# 2014_AlimBeaconEye.net
KiCad netlist of a schematic drawn in Altium Designer
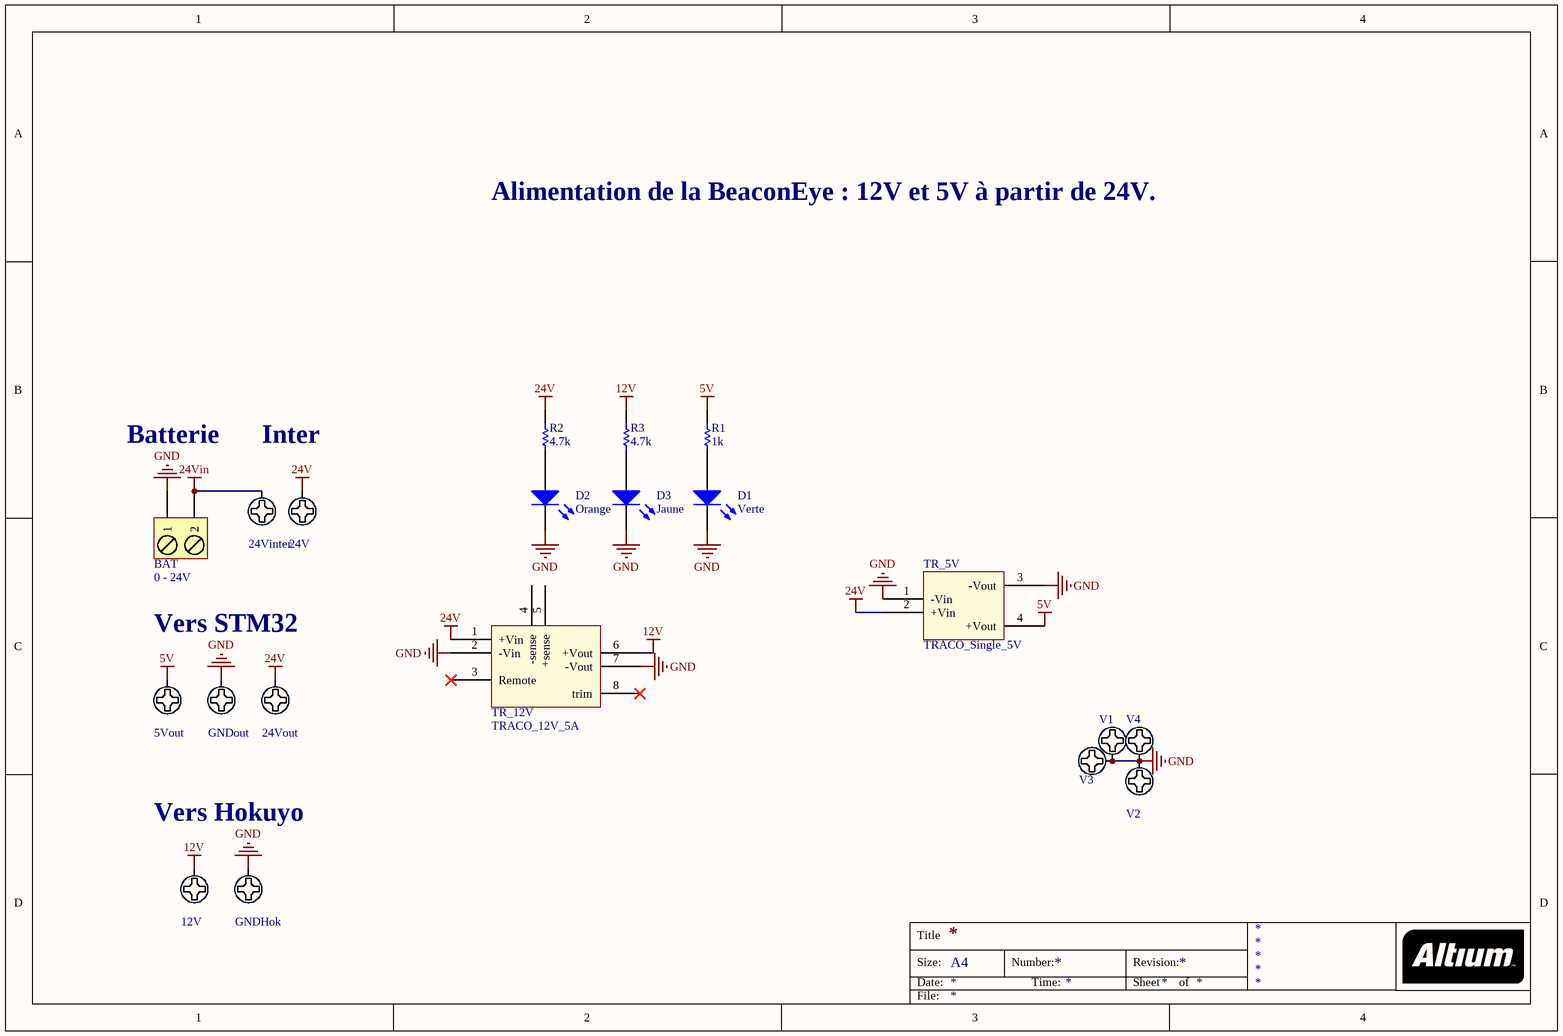
[diagram p0: 2014_AlimBeaconEye.SchDoc]

(export (version "E")
  (design (tool "Eeschema 10.0.6"))
  (components
    (comp (ref "5Vout")
      (value "Pad_M3")
      (footprint "M3x6mm")
      (description "Vis M3 X 6mm _TORX_Tête 6mm")
      (fields (field (name "PUBLISHER") "Damien Guitton"))
      (libsource (lib "_ROBOT") (part "Vis M3 X 6mm _TORX_Tête 6mm"))
    )
    (comp (ref "12V")
      (value "Pad_M3")
      (footprint "M3x6mm")
      (description "Vis M3 X 6mm _TORX_Tête 6mm")
      (fields (field (name "PUBLISHER") "Damien Guitton"))
      (libsource (lib "_ROBOT") (part "Vis M3 X 6mm _TORX_Tête 6mm"))
    )
    (comp (ref "24V")
      (value "Pad_M3")
      (footprint "M3x6mm")
      (description "Vis M3 X 6mm _TORX_Tête 6mm")
      (fields (field (name "PUBLISHER") "Damien Guitton"))
      (libsource (lib "_ROBOT") (part "Vis M3 X 6mm _TORX_Tête 6mm"))
    )
    (comp (ref "24Vinter")
      (value "Pad_M3")
      (footprint "M3x6mm")
      (description "Vis M3 X 6mm _TORX_Tête 6mm")
      (fields (field (name "PUBLISHER") "Damien Guitton"))
      (libsource (lib "_ROBOT") (part "Vis M3 X 6mm _TORX_Tête 6mm"))
    )
    (comp (ref "24Vout")
      (value "Pad_M3")
      (footprint "M3x6mm")
      (description "Vis M3 X 6mm _TORX_Tête 6mm")
      (fields (field (name "PUBLISHER") "Damien Guitton"))
      (libsource (lib "_ROBOT") (part "Vis M3 X 6mm _TORX_Tête 6mm"))
    )
    (comp (ref "BAT")
      (value "0 - 24V")
      (footprint "BORNIER2_FEM_COUDE")
      (description "Terminal blocks, 2 pins, pitch=5mm")
      (libsource (lib "miniprojet") (part "BORNIER2"))
    )
    (comp (ref "D1")
      (value "Verte")
      (footprint "LED_0805")
      (description "Typical LED")
      (fields (field (name "PUBLISHER") "Altium Limited"))
      (libsource (lib "_ROBOT") (part "LED"))
    )
    (comp (ref "D2")
      (value "Orange")
      (footprint "LED_0805")
      (description "Typical LED")
      (fields (field (name "PUBLISHER") "Altium Limited"))
      (libsource (lib "_ROBOT") (part "LED"))
    )
    (comp (ref "D3")
      (value "Jaune")
      (footprint "LED_0805")
      (description "Typical LED")
      (fields (field (name "PUBLISHER") "Altium Limited"))
      (libsource (lib "_ROBOT") (part "LED"))
    )
    (comp (ref "GNDHok")
      (value "Pad_M3")
      (footprint "M3x6mm")
      (description "Vis M3 X 6mm _TORX_Tête 6mm")
      (fields (field (name "PUBLISHER") "Damien Guitton"))
      (libsource (lib "_ROBOT") (part "Vis M3 X 6mm _TORX_Tête 6mm"))
    )
    (comp (ref "GNDout")
      (value "Pad_M3")
      (footprint "M3x6mm")
      (description "Vis M3 X 6mm _TORX_Tête 6mm")
      (fields (field (name "PUBLISHER") "Damien Guitton"))
      (libsource (lib "_ROBOT") (part "Vis M3 X 6mm _TORX_Tête 6mm"))
    )
    (comp (ref "R1")
      (value "1k")
      (footprint "R1206_N")
      (description "Resistor")
      (fields (field (name "PUBLISHER") "Altium Limited"))
      (libsource (lib "_ROBOT") (part "Resistor"))
    )
    (comp (ref "R2")
      (value "4.7k")
      (footprint "R1206_N")
      (description "Resistor")
      (fields (field (name "PUBLISHER") "Altium Limited"))
      (libsource (lib "_ROBOT") (part "Resistor"))
    )
    (comp (ref "R3")
      (value "4.7k")
      (footprint "R1206_N")
      (description "Resistor")
      (fields (field (name "PUBLISHER") "Altium Limited"))
      (libsource (lib "_ROBOT") (part "Resistor"))
    )
    (comp (ref "TR_5V")
      (value "TRACO_Single_5V")
      (footprint "TRACO_Single")
      (libsource (lib "Robot2010") (part "TRACO_Single"))
    )
    (comp (ref "TR_12V")
      (value "TRACO_12V_5A")
      (footprint "TRACO_SIMPLE_12V_5A")
      (libsource (lib "_ROBOT") (part "TRACO_12V_5A"))
    )
    (comp (ref "V1")
      (value "Pad_M3")
      (footprint "M3x6mm")
      (description "Vis M3 X 6mm _TORX_Tête 6mm")
      (fields (field (name "PUBLISHER") "Damien Guitton"))
      (libsource (lib "_ROBOT") (part "Vis M3 X 6mm _TORX_Tête 6mm"))
    )
    (comp (ref "V2")
      (value "Pad_M3")
      (footprint "M3x6mm")
      (description "Vis M3 X 6mm _TORX_Tête 6mm")
      (fields (field (name "PUBLISHER") "Damien Guitton"))
      (libsource (lib "_ROBOT") (part "Vis M3 X 6mm _TORX_Tête 6mm"))
    )
    (comp (ref "V3")
      (value "Pad_M3")
      (footprint "M3x6mm")
      (description "Vis M3 X 6mm _TORX_Tête 6mm")
      (fields (field (name "PUBLISHER") "Damien Guitton"))
      (libsource (lib "_ROBOT") (part "Vis M3 X 6mm _TORX_Tête 6mm"))
    )
    (comp (ref "V4")
      (value "Pad_M3")
      (footprint "M3x6mm")
      (description "Vis M3 X 6mm _TORX_Tête 6mm")
      (fields (field (name "PUBLISHER") "Damien Guitton"))
      (libsource (lib "_ROBOT") (part "Vis M3 X 6mm _TORX_Tête 6mm"))
    )
  )
  (nets
    (net (code "1") (name "5V") (class "Default")
      (node (ref "5Vout") (pin "1") (pinfunction "1_1") (pintype "passive"))
      (node (ref "R1") (pin "1") (pinfunction "1_1") (pintype "passive"))
      (node (ref "TR_5V") (pin "4") (pinfunction "+Vout_4") (pintype "passive"))
    )
    (net (code "2") (name "12V") (class "Default")
      (node (ref "12V") (pin "1") (pinfunction "1_1") (pintype "passive"))
      (node (ref "R3") (pin "1") (pinfunction "1_1") (pintype "passive"))
      (node (ref "TR_12V") (pin "6") (pinfunction "+Vout_6") (pintype "passive"))
    )
    (net (code "3") (name "24V") (class "Default")
      (node (ref "24V") (pin "1") (pinfunction "1_1") (pintype "passive"))
      (node (ref "24Vout") (pin "1") (pinfunction "1_1") (pintype "passive"))
      (node (ref "R2") (pin "1") (pinfunction "1_1") (pintype "passive"))
      (node (ref "TR_12V") (pin "1") (pinfunction "+Vin_1") (pintype "passive"))
      (node (ref "TR_5V") (pin "2") (pinfunction "+Vin_2") (pintype "passive"))
    )
    (net (code "4") (name "24Vin") (class "Default")
      (node (ref "24Vinter") (pin "1") (pinfunction "1_1") (pintype "passive"))
      (node (ref "BAT") (pin "2") (pinfunction "2_2") (pintype "passive"))
    )
    (net (code "5") (name "GND") (class "Default")
      (node (ref "BAT") (pin "1") (pinfunction "1_1") (pintype "passive"))
      (node (ref "D1") (pin "2") (pinfunction "K_2") (pintype "passive"))
      (node (ref "D2") (pin "2") (pinfunction "K_2") (pintype "passive"))
      (node (ref "D3") (pin "2") (pinfunction "K_2") (pintype "passive"))
      (node (ref "GNDHok") (pin "1") (pinfunction "1_1") (pintype "passive"))
      (node (ref "GNDout") (pin "1") (pinfunction "1_1") (pintype "passive"))
      (node (ref "TR_12V") (pin "2") (pinfunction "-Vin_2") (pintype "passive"))
      (node (ref "TR_12V") (pin "7") (pinfunction "-Vout_7") (pintype "passive"))
      (node (ref "TR_5V") (pin "1") (pinfunction "-Vin_1") (pintype "passive"))
      (node (ref "TR_5V") (pin "3") (pinfunction "-Vout_3") (pintype "passive"))
      (node (ref "V1") (pin "1") (pinfunction "1_1") (pintype "passive"))
      (node (ref "V2") (pin "1") (pinfunction "1_1") (pintype "passive"))
      (node (ref "V3") (pin "1") (pinfunction "1_1") (pintype "passive"))
      (node (ref "V4") (pin "1") (pinfunction "1_1") (pintype "passive"))
    )
    (net (code "6") (name "Net-(D1-A)") (class "Default")
      (node (ref "D1") (pin "1") (pinfunction "A_1") (pintype "passive"))
      (node (ref "R1") (pin "2") (pinfunction "2_2") (pintype "passive"))
    )
    (net (code "7") (name "Net-(D2-A)") (class "Default")
      (node (ref "D2") (pin "1") (pinfunction "A_1") (pintype "passive"))
      (node (ref "R2") (pin "2") (pinfunction "2_2") (pintype "passive"))
    )
    (net (code "8") (name "Net-(D3-A)") (class "Default")
      (node (ref "D3") (pin "1") (pinfunction "A_1") (pintype "passive"))
      (node (ref "R3") (pin "2") (pinfunction "2_2") (pintype "passive"))
    )
    (net (code "9") (name "unconnected-(TR_12V-+sense-Pad5)") (class "Default")
      (node (ref "TR_12V") (pin "5") (pinfunction "+sense_5") (pintype "passive"))
    )
    (net (code "10") (name "unconnected-(TR_12V--sense-Pad4)") (class "Default")
      (node (ref "TR_12V") (pin "4") (pinfunction "-sense_4") (pintype "passive"))
    )
    (net (code "11") (name "unconnected-(TR_12V-Remote-Pad3)") (class "Default")
      (node (ref "TR_12V") (pin "3") (pinfunction "Remote_3") (pintype "passive+no_connect"))
    )
    (net (code "12") (name "unconnected-(TR_12V-trim-Pad8)") (class "Default")
      (node (ref "TR_12V") (pin "8") (pinfunction "trim_8") (pintype "passive"))
    )
  )
)
